# EFR32BG13_IO_Port_Pins.net
KiCad netlist of a schematic drawn in Altium Designer
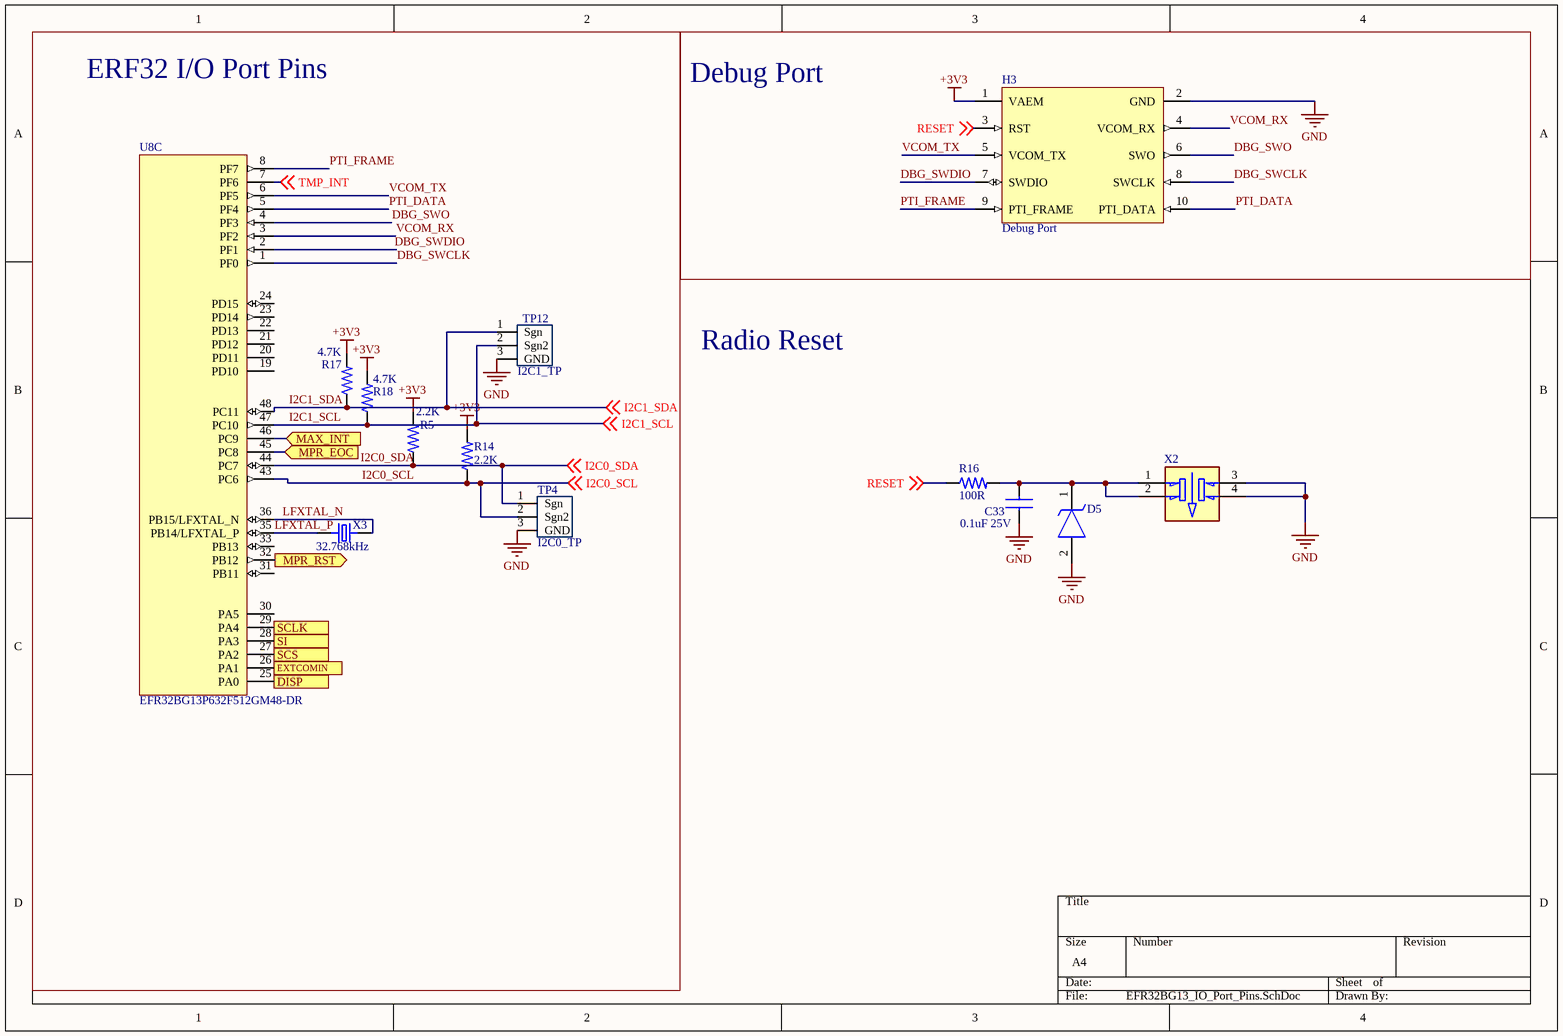
[diagram p0: EFR32BG13_IO_Port_Pins.SchDoc]

(export (version "E")
  (design (tool "Eeschema 10.0.6"))
  (components
    (comp (ref "C33")
      (value "0.1uF 25V")
      (footprint "Chip2Pin_1.6x0.8x0.9_CAP")
      (description "Cap Ceramic 0.1uF 25V X7R 10% Pad SMD 0603 Soft Termination 125C Automotive T/R")
      (fields
        (field (name "MANUFACTURER") "Murata")
        (field (name "MANUFACTURER PART NUMBER") "GCJ188R71E104KA12D")
      )
      (libsource (lib "LPEDT_Parts") (part "GCJ188R71E104KA12D"))
    )
    (comp (ref "D5")
      (value "TVS DIODE 5.5VWM 12VC SOD923")
      (footprint "SODFL1006X40N")
      (description "ESD Suppressors / TVS Diodes Bi-Directional 35pF Dataline Protection")
      (fields (field (name "MANUFACTURER") "Diodes") (field (name "MANUFACTURER PART NUMBER") "D5V0M1U2S9-7"))
      (libsource (lib "LPEDT_Parts") (part "D5V0M1U2S9-7"))
    )
    (comp (ref "H3")
      (value "Debug Port")
      (footprint "Amphenol_20021121_0")
      (description "CONN HEADER SMD 10POS 1.27MM. Connector Header Surface Mount 10 position 0.050\"")
      (fields
        (field (name "MANUFACTURER") "Amphenol ICC / FCI")
        (field (name "MANUFACTURER PART NUMBER") "20021121-00010C1LF")
      )
      (libsource (lib "LPEDT_Parts") (part "20021121-00010C1LF"))
    )
    (comp (ref "R5")
      (value "2.2K")
      (footprint "RES_0603_1608X06")
      (description "Res Thick Film 0603 2.2K Ohm 1% 0.1W(1/10W) ±100ppm/°C Pad SMD T/R")
      (fields
        (field (name "MANUFACTURER") "Yageo")
        (field (name "MANUFACTURER PART NUMBER") "RC0603FR-072K2L")
      )
      (libsource (lib "LPEDT_Parts") (part "RC0603FR-072K2L"))
    )
    (comp (ref "R14")
      (value "2.2K")
      (footprint "RES_0603_1608X06")
      (description "Res Thick Film 0603 2.2K Ohm 1% 0.1W(1/10W) ±100ppm/°C Pad SMD T/R")
      (fields
        (field (name "MANUFACTURER") "Yageo")
        (field (name "MANUFACTURER PART NUMBER") "RC0603FR-072K2L")
      )
      (libsource (lib "LPEDT_Parts") (part "RC0603FR-072K2L"))
    )
    (comp (ref "R16")
      (value "100R")
      (footprint "RES_0603_1608X06")
      (description "Res Thick Film 0603 100 Ohm 5% 1/10W ±100ppm/°C Molded SMD SMD Paper T/R")
      (fields
        (field (name "MANUFACTURER") "Yageo")
        (field (name "MANUFACTURER PART NUMBER") "RC0603JR-07100RL")
      )
      (libsource (lib "LPEDT_Parts") (part "RC0603JR-07100RL"))
    )
    (comp (ref "R17")
      (value "4.7K")
      (footprint "RES_0603_1608X06")
      (description "Res General Purpose Thick Film 0603 4.7k Ohm 5% 1/10W ±100ppm/°C Molded Paper T/R")
      (fields
        (field (name "MANUFACTURER") "Yageo")
        (field (name "MANUFACTURER PART NUMBER") "RC0603JR-074K7L")
      )
      (libsource (lib "LPEDT_Parts") (part "RC0603JR-074K7L"))
    )
    (comp (ref "R18")
      (value "4.7K")
      (footprint "RES_0603_1608X06")
      (description "Res General Purpose Thick Film 0603 4.7k Ohm 5% 1/10W ±100ppm/°C Molded Paper T/R")
      (fields
        (field (name "MANUFACTURER") "Yageo")
        (field (name "MANUFACTURER PART NUMBER") "RC0603JR-074K7L")
      )
      (libsource (lib "LPEDT_Parts") (part "RC0603JR-074K7L"))
    )
    (comp (ref "TP4")
      (value "I2C0_TP")
      (footprint "TP10x_Floating_3PIN")
      (libsource (lib "LPEDT_Parts") (part "10X_FLOAT_3PIN_TP"))
    )
    (comp (ref "TP12")
      (value "I2C1_TP")
      (footprint "TP10x_Floating_3PIN")
      (libsource (lib "LPEDT_Parts") (part "10X_FLOAT_3PIN_TP"))
    )
    (comp (ref "U8")
      (value "EFR32BG13P632F512GM48-DR")
      (footprint "QFN_48_7X7")
      (description "Blue Gecko BLE Soc QFN48 2.4 G 10 dB BLE/Proprietary 512 kB 64 kB(RAM) 31GPIO")
      (fields (field (name "MANUFACTURER") "Silicon Labs"))
      (libsource (lib "LPEDT_Parts") (part "EFR32BG13P632F512GM48-DR"))
    )
    (comp (ref "X2")
      (value "SWITCH TACTILE SPST-NO 0.05A 42V")
      (footprint "1241160111")
      (description "Switch Tactile N.O. SPST Round Button J-Lead 0.05A 30VAC 42VDC 0.12VA >1000000Cycles 1.6N SMD Box")
      (fields
        (field (name "MANUFACTURER") "Schurter")
        (field (name "MANUFACTURER PART NUMBER") "1241.1601.11")
      )
      (libsource (lib "LPEDT_Parts") (part "1241.1601.11"))
    )
    (comp (ref "X3")
      (value "32.768kHz")
      (footprint "XTAL_ECS-.327-7-34B-TR")
      (description "32.768kHz Â±20ppm Crystal 7pF 70 kOhms 2-SMD, No Lead")
      (fields (field (name "MP") "ECS-.327-7-34B-TR") (field (name "MF") "ECS Inc."))
      (libsource (lib "LPEDT_Parts") (part "ECS-.327-7-34B-TR"))
    )
  )
  (nets
    (net (code "1") (name "+3V3") (class "Default")
      (node (ref "H3") (pin "1") (pinfunction "VAEM_1") (pintype "power_in"))
      (node (ref "R14") (pin "2") (pinfunction "2_2") (pintype "passive"))
      (node (ref "R17") (pin "2") (pinfunction "2_2") (pintype "passive"))
      (node (ref "R18") (pin "2") (pinfunction "2_2") (pintype "passive"))
      (node (ref "R5") (pin "2") (pinfunction "2_2") (pintype "passive"))
    )
    (net (code "2") (name "/DBG_SWCLK") (class "Default")
      (node (ref "H3") (pin "8") (pinfunction "SWCLK_8") (pintype "input"))
      (node (ref "U8") (pin "1") (pinfunction "PF0_1") (pintype "output"))
    )
    (net (code "3") (name "/DBG_SWDIO") (class "Default")
      (node (ref "H3") (pin "7") (pinfunction "SWDIO_7") (pintype "bidirectional"))
      (node (ref "U8") (pin "2") (pinfunction "PF1_2") (pintype "input"))
    )
    (net (code "4") (name "/DBG_SWO") (class "Default")
      (node (ref "H3") (pin "6") (pinfunction "SWO_6") (pintype "output"))
      (node (ref "U8") (pin "4") (pinfunction "PF3_4") (pintype "input"))
    )
    (net (code "5") (name "/DISP") (class "Default")
      (node (ref "U8") (pin "25") (pinfunction "PA0_25") (pintype "passive"))
    )
    (net (code "6") (name "/EXTCOMIN") (class "Default")
      (node (ref "U8") (pin "26") (pinfunction "PA1_26") (pintype "passive"))
    )
    (net (code "7") (name "/LFXTAL_N") (class "Default")
      (node (ref "U8") (pin "36") (pinfunction "PB15/LFXTAL_N_36") (pintype "bidirectional"))
      (node (ref "X3") (pin "2") (pinfunction "2_2") (pintype "passive"))
    )
    (net (code "8") (name "/LFXTAL_P") (class "Default")
      (node (ref "U8") (pin "35") (pinfunction "PB14/LFXTAL_P_35") (pintype "bidirectional"))
      (node (ref "X3") (pin "1") (pinfunction "1_1") (pintype "passive"))
    )
    (net (code "9") (name "/MAX_INT") (class "Default")
      (node (ref "U8") (pin "46") (pinfunction "PC9_46") (pintype "passive"))
    )
    (net (code "10") (name "/MPR_EOC") (class "Default")
      (node (ref "U8") (pin "45") (pinfunction "PC8_45") (pintype "passive"))
    )
    (net (code "11") (name "/MPR_RST") (class "Default")
      (node (ref "U8") (pin "32") (pinfunction "PB12_32") (pintype "output"))
    )
    (net (code "12") (name "/PTI_DATA") (class "Default")
      (node (ref "H3") (pin "10") (pinfunction "PTI_DATA_10") (pintype "input"))
      (node (ref "U8") (pin "5") (pinfunction "PF4_5") (pintype "output"))
    )
    (net (code "13") (name "/PTI_FRAME") (class "Default")
      (node (ref "H3") (pin "9") (pinfunction "PTI_FRAME_9") (pintype "input"))
      (node (ref "U8") (pin "8") (pinfunction "PF7_8") (pintype "output"))
    )
    (net (code "14") (name "/SCLK") (class "Default")
      (node (ref "U8") (pin "29") (pinfunction "PA4_29") (pintype "passive"))
    )
    (net (code "15") (name "/SCS") (class "Default")
      (node (ref "U8") (pin "27") (pinfunction "PA2_27") (pintype "passive"))
    )
    (net (code "16") (name "/SI") (class "Default")
      (node (ref "U8") (pin "28") (pinfunction "PA3_28") (pintype "passive"))
    )
    (net (code "17") (name "/VCOM_RX") (class "Default")
      (node (ref "H3") (pin "4") (pinfunction "VCOM_RX_4") (pintype "output"))
      (node (ref "U8") (pin "3") (pinfunction "PF2_3") (pintype "input"))
    )
    (net (code "18") (name "/VCOM_TX") (class "Default")
      (node (ref "H3") (pin "5") (pinfunction "VCOM_TX_5") (pintype "input"))
      (node (ref "U8") (pin "6") (pinfunction "PF5_6") (pintype "output"))
    )
    (net (code "19") (name "GND") (class "Default")
      (node (ref "C33") (pin "2") (pinfunction "2_2") (pintype "passive"))
      (node (ref "D5") (pin "2") (pinfunction "A_2") (pintype "passive"))
      (node (ref "H3") (pin "2") (pinfunction "GND_2") (pintype "passive"))
      (node (ref "TP12") (pin "3") (pinfunction "GND_3") (pintype "passive"))
      (node (ref "TP4") (pin "3") (pinfunction "GND_3") (pintype "passive"))
      (node (ref "X2") (pin "3") (pinfunction "NC2_3") (pintype "passive"))
      (node (ref "X2") (pin "4") (pinfunction "COM2_4") (pintype "passive"))
    )
    (net (code "20") (name "I2C0_SCL") (class "Default")
      (node (ref "R14") (pin "1") (pinfunction "1_1") (pintype "passive"))
      (node (ref "TP4") (pin "2") (pinfunction "Sgn2_2") (pintype "passive"))
      (node (ref "U8") (pin "43") (pinfunction "PC6_43") (pintype "output"))
    )
    (net (code "21") (name "I2C0_SDA") (class "Default")
      (node (ref "R5") (pin "1") (pinfunction "1_1") (pintype "passive"))
      (node (ref "TP4") (pin "1") (pinfunction "Sgn_1") (pintype "passive"))
      (node (ref "U8") (pin "44") (pinfunction "PC7_44") (pintype "bidirectional"))
    )
    (net (code "22") (name "I2C1_SCL") (class "Default")
      (node (ref "R18") (pin "1") (pinfunction "1_1") (pintype "passive"))
      (node (ref "TP12") (pin "2") (pinfunction "Sgn2_2") (pintype "passive"))
      (node (ref "U8") (pin "47") (pinfunction "PC10_47") (pintype "output"))
    )
    (net (code "23") (name "I2C1_SDA") (class "Default")
      (node (ref "R17") (pin "1") (pinfunction "1_1") (pintype "passive"))
      (node (ref "TP12") (pin "1") (pinfunction "Sgn_1") (pintype "passive"))
      (node (ref "U8") (pin "48") (pinfunction "PC11_48") (pintype "bidirectional"))
    )
    (net (code "24") (name "Net-(D5-K)") (class "Default")
      (node (ref "C33") (pin "1") (pinfunction "1_1") (pintype "passive"))
      (node (ref "D5") (pin "1") (pinfunction "K_1") (pintype "passive"))
      (node (ref "R16") (pin "2") (pinfunction "2_2") (pintype "passive"))
      (node (ref "X2") (pin "1") (pinfunction "NC1_1") (pintype "passive"))
      (node (ref "X2") (pin "2") (pinfunction "COM1_2") (pintype "passive"))
    )
    (net (code "25") (name "RESET") (class "Default")
      (node (ref "H3") (pin "3") (pinfunction "RST_3") (pintype "input"))
      (node (ref "R16") (pin "1") (pinfunction "1_1") (pintype "passive"))
    )
    (net (code "26") (name "TMP_INT") (class "Default")
      (node (ref "U8") (pin "7") (pinfunction "PF6_7") (pintype "passive"))
    )
    (net (code "27") (name "unconnected-(U8C-PA5-Pad30)") (class "Default")
      (node (ref "U8") (pin "30") (pinfunction "PA5_30") (pintype "passive"))
    )
    (net (code "28") (name "unconnected-(U8C-PB11-Pad31)") (class "Default")
      (node (ref "U8") (pin "31") (pinfunction "PB11_31") (pintype "bidirectional"))
    )
    (net (code "29") (name "unconnected-(U8C-PB13-Pad33)") (class "Default")
      (node (ref "U8") (pin "33") (pinfunction "PB13_33") (pintype "bidirectional"))
    )
    (net (code "30") (name "unconnected-(U8C-PD10-Pad19)") (class "Default")
      (node (ref "U8") (pin "19") (pinfunction "PD10_19") (pintype "passive"))
    )
    (net (code "31") (name "unconnected-(U8C-PD11-Pad20)") (class "Default")
      (node (ref "U8") (pin "20") (pinfunction "PD11_20") (pintype "passive"))
    )
    (net (code "32") (name "unconnected-(U8C-PD12-Pad21)") (class "Default")
      (node (ref "U8") (pin "21") (pinfunction "PD12_21") (pintype "passive"))
    )
    (net (code "33") (name "unconnected-(U8C-PD13-Pad22)") (class "Default")
      (node (ref "U8") (pin "22") (pinfunction "PD13_22") (pintype "passive"))
    )
    (net (code "34") (name "unconnected-(U8C-PD14-Pad23)") (class "Default")
      (node (ref "U8") (pin "23") (pinfunction "PD14_23") (pintype "output"))
    )
    (net (code "35") (name "unconnected-(U8C-PD15-Pad24)") (class "Default")
      (node (ref "U8") (pin "24") (pinfunction "PD15_24") (pintype "bidirectional"))
    )
  )
)
